# LDO-LM1117.net
KiCad netlist of a schematic drawn in Altium Designer
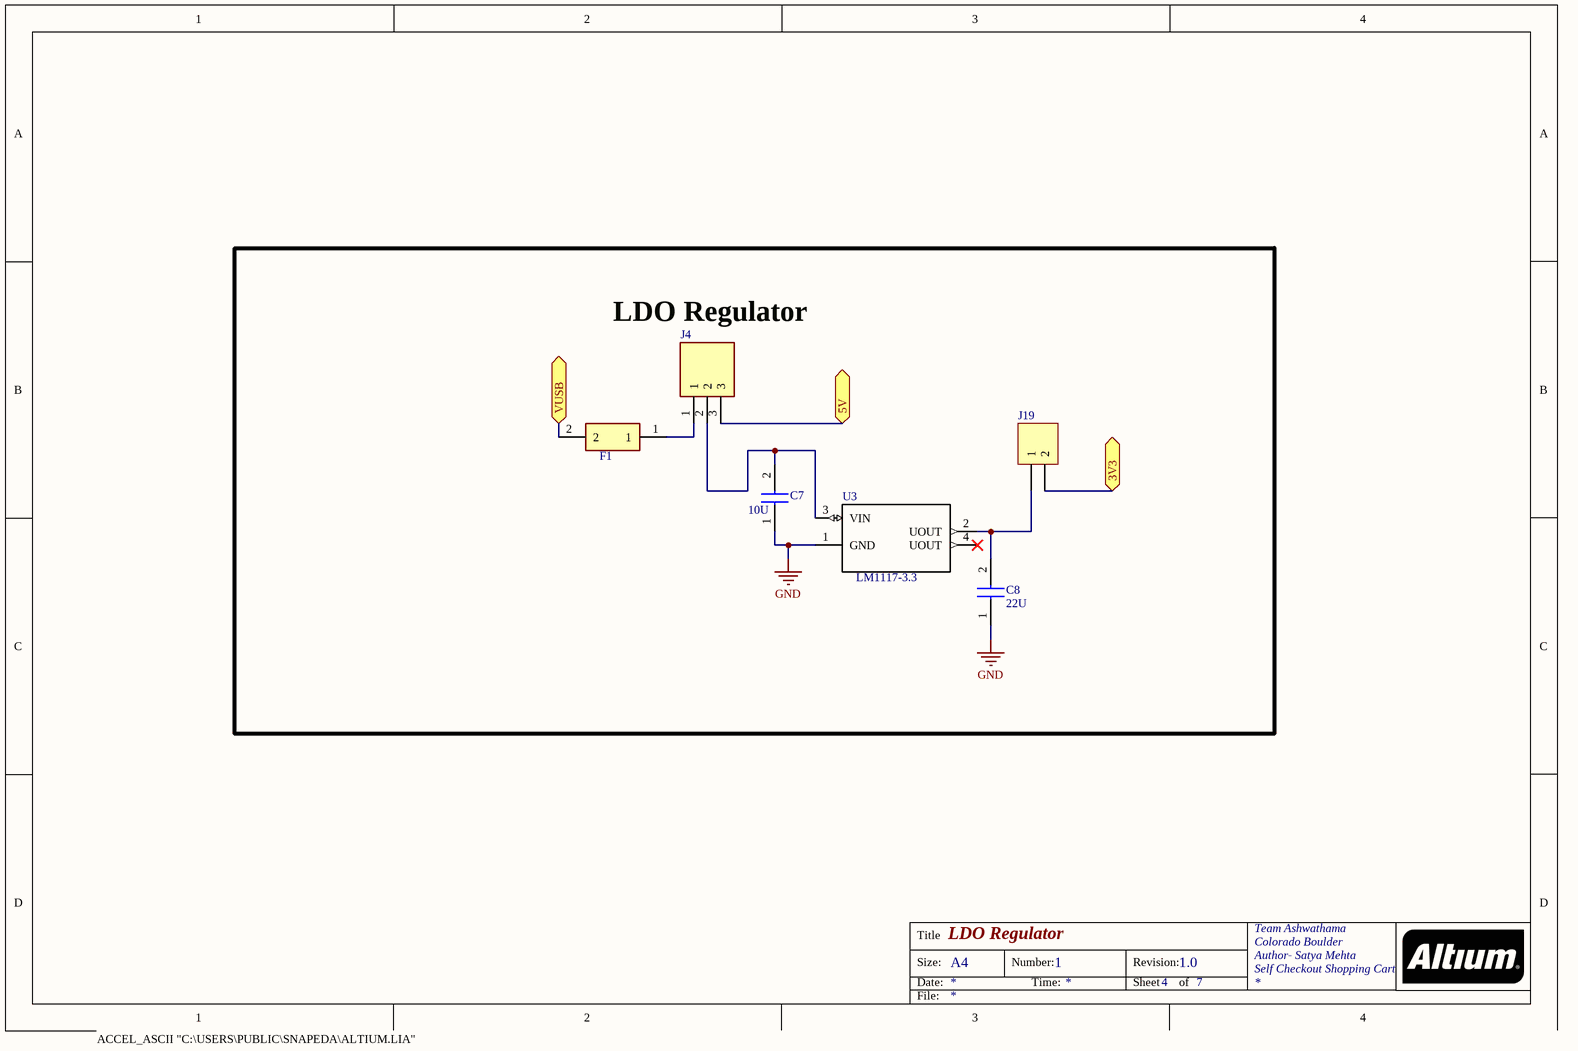
[diagram p0: LDO-LM1117.SchDoc]

(export (version "E")
  (design (tool "Eeschema 10.0.6"))
  (components
    (comp (ref "C7")
      (value "10U")
      (footprint "SamacSys:CAPC6153X300N")
      (description "Capacitor")
      (fields
        (field (name "MANUFACTURER_PART_NUMBER") "KCM55LR71E156KH01K")
        (field (name "MOUSER PART NUMBER") "81-KCM55LR71E156KH1K")
      )
      (libsource (lib "*") (part "KCM55LR71E156KH01K"))
    )
    (comp (ref "C8")
      (value "22U")
      (footprint "SamacSys:CAPC3225X270N")
      (description "Capacitor")
      (fields
        (field (name "MANUFACTURER_PART_NUMBER") "GRM32ER71C226KEA8L")
        (field (name "MOUSER PART NUMBER") "81-GRM32ER71C226KEAL")
      )
      (libsource (lib "*") (part "GRM32ER71C226KEA8L"))
    )
    (comp (ref "F1")
      (value "MF-MSMF050-2")
      (footprint "Library_Cart:FUSC4632X85N")
      (description "Fuse")
      (fields
        (field (name "MOUSER PART NUMBER") "652-MF-MSMF050-2")
        (field (name "RS PART NUMBER") "6478156P")
      )
      (libsource (lib "*") (part "MF-MSMF050-2"))
    )
    (comp (ref "J4")
      (value "61900311121")
      (footprint "SamacSys:SHDR3W64P0X254_1X3_766X580X1175P")
      (description "Connector")
      (fields
        (field (name "MOUSER PART NUMBER") "710-61900311121")
        (field (name "RS PART NUMBER") "8281474P")
      )
      (libsource (lib "*") (part "61900311121"))
    )
    (comp (ref "J19")
      (value "Header 2")
      (footprint "HDR1X2")
      (description "Header, 2-Pin")
      (fields
        (field (name "MANUFACTURER_PART_NUMBER") "BG301-04-A-0540-L-B")
        (field (name "DIGI-KEY PART NUMBER") "2073-BG301-02-A-0540-L-BCT-ND")
      )
      (libsource (lib "Miscellaneous Connectors") (part "Header 2"))
    )
    (comp (ref "U3")
      (value "LM1117-3.3")
      (footprint "*SOT-223")
      (description "3V3 Low Dropout Regulator")
      (fields
        (field (name "MANUFACTURER_PART_NUMBER") "LM1117MPX-3.3/NOPB")
        (field (name "MOUSER PART NUMBER") "926-LM1117MPX3.3NOPB")
      )
      (libsource (lib "LM1117-3.3") (part "LM1117-3.3"))
    )
  )
  (nets
    (net (code "1") (name "/3V3") (class "Default")
      (node (ref "J19") (pin "2") (pinfunction "2_2") (pintype "passive"))
    )
    (net (code "2") (name "/5V") (class "Default")
      (node (ref "J4") (pin "3") (pinfunction "3_3") (pintype "passive"))
    )
    (net (code "3") (name "/VUSB") (class "Default")
      (node (ref "F1") (pin "2") (pinfunction "2_2") (pintype "passive"))
    )
    (net (code "4") (name "GND") (class "Default")
      (node (ref "C7") (pin "1") (pinfunction "1_1") (pintype "passive"))
      (node (ref "C8") (pin "1") (pinfunction "1_1") (pintype "passive"))
      (node (ref "U3") (pin "1") (pinfunction "GND_1") (pintype "passive"))
    )
    (net (code "5") (name "Net-(C8-Pad2)") (class "Default")
      (node (ref "C8") (pin "2") (pinfunction "2_2") (pintype "passive"))
      (node (ref "J19") (pin "1") (pinfunction "1_1") (pintype "passive"))
      (node (ref "U3") (pin "2") (pinfunction "UOUT_2") (pintype "output"))
    )
    (net (code "6") (name "Net-(F1-Pad1)") (class "Default")
      (node (ref "F1") (pin "1") (pinfunction "1_1") (pintype "passive"))
      (node (ref "J4") (pin "1") (pinfunction "1_1") (pintype "passive"))
    )
    (net (code "7") (name "Net-(U3-VIN)") (class "Default")
      (node (ref "C7") (pin "2") (pinfunction "2_2") (pintype "passive"))
      (node (ref "J4") (pin "2") (pinfunction "2_2") (pintype "passive"))
      (node (ref "U3") (pin "3") (pinfunction "VIN_3") (pintype "bidirectional"))
    )
    (net (code "8") (name "unconnected-(U3-UOUT-Pad4)") (class "Default")
      (node (ref "U3") (pin "4") (pinfunction "UOUT_4") (pintype "output+no_connect"))
    )
  )
)
